# pcb_06.net
KiCad netlist of a schematic drawn in EAGLE
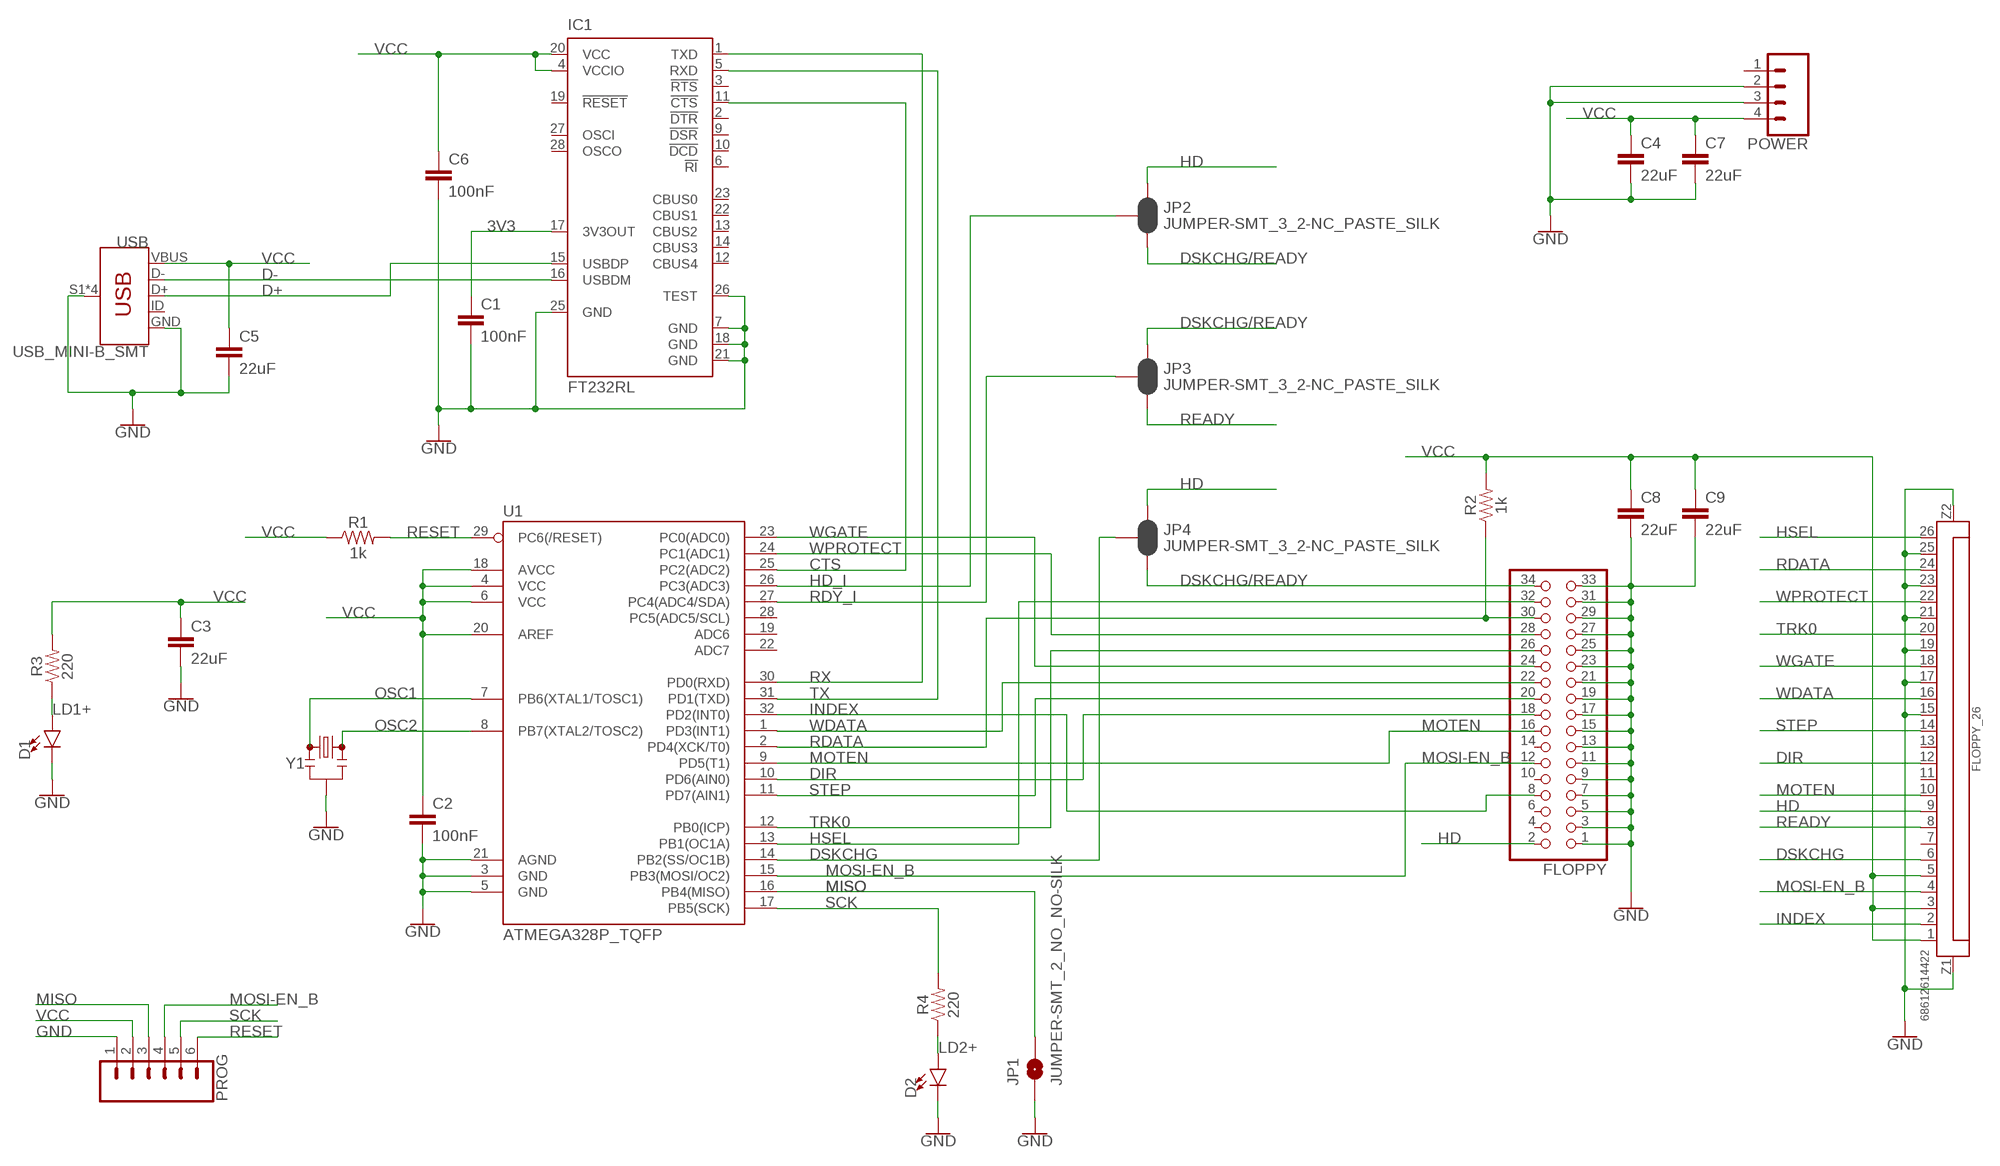
[diagram p0: schematic, sheet 1]

(export (version "E")
  (design (tool "Eeschema 10.0.6"))
  (components
    (comp (ref "C1")
      (value "100nF")
      (footprint "eagle-import:0603")
      (libsource (lib "eagle-import") (part "1.0UF-0603-16V-10%"))
    )
    (comp (ref "C2")
      (value "100nF")
      (footprint "eagle-import:0603")
      (libsource (lib "eagle-import") (part "1.0UF-0603-16V-10%"))
    )
    (comp (ref "C3")
      (value "22uF")
      (footprint "eagle-import:C0805")
      (libsource (lib "eagle-import") (part "C-EUC0805"))
    )
    (comp (ref "C4")
      (value "22uF")
      (footprint "eagle-import:C0805")
      (libsource (lib "eagle-import") (part "C-EUC0805"))
    )
    (comp (ref "C5")
      (value "22uF")
      (footprint "eagle-import:C0805")
      (libsource (lib "eagle-import") (part "C-EUC0805"))
    )
    (comp (ref "C6")
      (value "100nF")
      (footprint "eagle-import:0603")
      (libsource (lib "eagle-import") (part "1.0UF-0603-16V-10%"))
    )
    (comp (ref "C7")
      (value "22uF")
      (footprint "eagle-import:C0805")
      (libsource (lib "eagle-import") (part "C-EUC0805"))
    )
    (comp (ref "C8")
      (value "22uF")
      (footprint "eagle-import:C0805")
      (libsource (lib "eagle-import") (part "C-EUC0805"))
    )
    (comp (ref "C9")
      (value "22uF")
      (footprint "eagle-import:C0805")
      (libsource (lib "eagle-import") (part "C-EUC0805"))
    )
    (comp (ref "D1")
      (value "LED5MM")
      (footprint "eagle-import:LED_5MM")
      (libsource (lib "eagle-import") (part "LED5MM"))
    )
    (comp (ref "D2")
      (value "LED5MM")
      (footprint "eagle-import:LED_5MM")
      (libsource (lib "eagle-import") (part "LED5MM"))
    )
    (comp (ref "FLOPPY")
      (value "PINHD-2X17_2.54-90°")
      (footprint "eagle-import:2X17_90")
      (libsource (lib "eagle-import") (part "PINHD-2X17_2.54-90°"))
    )
    (comp (ref "FLOPPY_26")
      (value "68612614422")
      (footprint "eagle-import:68612614422")
      (libsource (lib "eagle-import") (part "6861XX14422_68612614422"))
    )
    (comp (ref "IC1")
      (value "FT232RL")
      (footprint "eagle-import:SSOP28")
      (libsource (lib "eagle-import") (part "FT232RL"))
    )
    (comp (ref "JP1")
      (value "JUMPER-SMT_2_NO_NO-SILK")
      (footprint "eagle-import:SMT-JUMPER_2_NO_NO-SILK")
      (libsource (lib "eagle-import") (part "JUMPER-SMT_2_NO_NO-SILK"))
    )
    (comp (ref "JP2")
      (value "JUMPER-SMT_3_2-NC_PASTE_SILK")
      (footprint "eagle-import:SMT-JUMPER_3_2-NC_PASTE_SILK")
      (libsource (lib "eagle-import") (part "JUMPER-SMT_3_2-NC_PASTE_SILK"))
    )
    (comp (ref "JP3")
      (value "JUMPER-SMT_3_2-NC_PASTE_SILK")
      (footprint "eagle-import:SMT-JUMPER_3_2-NC_PASTE_SILK")
      (libsource (lib "eagle-import") (part "JUMPER-SMT_3_2-NC_PASTE_SILK"))
    )
    (comp (ref "JP4")
      (value "JUMPER-SMT_3_2-NC_PASTE_SILK")
      (footprint "eagle-import:SMT-JUMPER_3_2-NC_PASTE_SILK")
      (libsource (lib "eagle-import") (part "JUMPER-SMT_3_2-NC_PASTE_SILK"))
    )
    (comp (ref "POWER")
      (value "CONN_04")
      (footprint "eagle-import:1X04")
      (libsource (lib "eagle-import") (part "CONN_04"))
    )
    (comp (ref "PROG")
      (value "CONN_06SILK_FEMALE_PTH")
      (footprint "eagle-import:1X06")
      (libsource (lib "eagle-import") (part "CONN_06SILK_FEMALE_PTH"))
    )
    (comp (ref "R1")
      (value "1k")
      (footprint "eagle-import:0603")
      (libsource (lib "eagle-import") (part "10KOHM-0603-1/10W-1%"))
    )
    (comp (ref "R2")
      (value "1k")
      (footprint "eagle-import:0603")
      (libsource (lib "eagle-import") (part "10KOHM-0603-1/10W-1%"))
    )
    (comp (ref "R3")
      (value "220")
      (footprint "eagle-import:0603")
      (libsource (lib "eagle-import") (part "10KOHM-0603-1/10W-1%"))
    )
    (comp (ref "R4")
      (value "220")
      (footprint "eagle-import:0603")
      (libsource (lib "eagle-import") (part "10KOHM-0603-1/10W-1%"))
    )
    (comp (ref "U1")
      (value "ATMEGA328P_TQFP")
      (footprint "eagle-import:TQFP32-08")
      (libsource (lib "eagle-import") (part "ATMEGA328P_TQFP"))
    )
    (comp (ref "USB")
      (value "USB_MINI-B_SMT")
      (footprint "eagle-import:USB-MINIB")
      (libsource (lib "eagle-import") (part "USB_MINI-B_SMT"))
    )
    (comp (ref "Y1")
      (value "RESONATORSMD-3.2X1.3")
      (footprint "eagle-import:RESONATOR-SMD-3.2X1.3")
      (libsource (lib "eagle-import") (part "RESONATORSMD-3.2X1.3"))
    )
  )
  (nets
    (net (code "1") (name "/3V3") (class "Default")
      (node (ref "C1") (pin "1") (pinfunction "1_1") (pintype "passive"))
      (node (ref "IC1") (pin "17") (pinfunction "3V3OUT_17") (pintype "output"))
    )
    (net (code "2") (name "/CTS") (class "Default")
      (node (ref "IC1") (pin "11") (pinfunction "~{CTS}_11") (pintype "input"))
      (node (ref "U1") (pin "25") (pinfunction "PC2(ADC2)_25") (pintype "bidirectional"))
    )
    (net (code "3") (name "/D+") (class "Default")
      (node (ref "IC1") (pin "15") (pinfunction "USBDP_15") (pintype "bidirectional"))
      (node (ref "USB") (pin "D+") (pinfunction "D+_D+") (pintype "bidirectional"))
    )
    (net (code "4") (name "/D-") (class "Default")
      (node (ref "IC1") (pin "16") (pinfunction "USBDM_16") (pintype "bidirectional"))
      (node (ref "USB") (pin "D-") (pinfunction "D-_D-") (pintype "bidirectional"))
    )
    (net (code "5") (name "/DIR") (class "Default")
      (node (ref "FLOPPY") (pin "18") (pinfunction "18_18") (pintype "passive"))
      (node (ref "FLOPPY_26") (pin "12") (pinfunction "12_12") (pintype "passive"))
      (node (ref "U1") (pin "10") (pinfunction "PD6(AIN0)_10") (pintype "bidirectional"))
    )
    (net (code "6") (name "/DSKCHG") (class "Default")
      (node (ref "FLOPPY_26") (pin "6") (pinfunction "6_6") (pintype "passive"))
      (node (ref "JP4") (pin "2") (pinfunction "2_2") (pintype "passive"))
      (node (ref "U1") (pin "14") (pinfunction "PB2(SS/OC1B)_14") (pintype "bidirectional"))
    )
    (net (code "7") (name "/DSKCHG{slash}READY") (class "Default")
      (node (ref "FLOPPY") (pin "34") (pinfunction "34_34") (pintype "passive"))
      (node (ref "JP2") (pin "3") (pinfunction "3_3") (pintype "passive"))
      (node (ref "JP3") (pin "1") (pinfunction "1_1") (pintype "passive"))
      (node (ref "JP4") (pin "3") (pinfunction "3_3") (pintype "passive"))
    )
    (net (code "8") (name "/HD") (class "Default")
      (node (ref "FLOPPY") (pin "2") (pinfunction "2_2") (pintype "passive"))
      (node (ref "FLOPPY_26") (pin "9") (pinfunction "9_9") (pintype "passive"))
      (node (ref "JP2") (pin "1") (pinfunction "1_1") (pintype "passive"))
      (node (ref "JP4") (pin "1") (pinfunction "1_1") (pintype "passive"))
    )
    (net (code "9") (name "/HD_I") (class "Default")
      (node (ref "JP2") (pin "2") (pinfunction "2_2") (pintype "passive"))
      (node (ref "U1") (pin "26") (pinfunction "PC3(ADC3)_26") (pintype "bidirectional"))
    )
    (net (code "10") (name "/HSEL") (class "Default")
      (node (ref "FLOPPY") (pin "32") (pinfunction "32_32") (pintype "passive"))
      (node (ref "FLOPPY_26") (pin "26") (pinfunction "26_26") (pintype "passive"))
      (node (ref "U1") (pin "13") (pinfunction "PB1(OC1A)_13") (pintype "bidirectional"))
    )
    (net (code "11") (name "/INDEX") (class "Default")
      (node (ref "FLOPPY") (pin "8") (pinfunction "8_8") (pintype "passive"))
      (node (ref "FLOPPY_26") (pin "2") (pinfunction "2_2") (pintype "passive"))
      (node (ref "U1") (pin "32") (pinfunction "PD2(INT0)_32") (pintype "bidirectional"))
    )
    (net (code "12") (name "/LD1+") (class "Default")
      (node (ref "D1") (pin "A") (pinfunction "A_A") (pintype "passive"))
      (node (ref "R3") (pin "1") (pinfunction "1_1") (pintype "passive"))
    )
    (net (code "13") (name "/LD2+") (class "Default")
      (node (ref "D2") (pin "A") (pinfunction "A_A") (pintype "passive"))
      (node (ref "R4") (pin "1") (pinfunction "1_1") (pintype "passive"))
    )
    (net (code "14") (name "/MISO") (class "Default")
      (node (ref "JP1") (pin "2") (pinfunction "2_2") (pintype "passive"))
      (node (ref "PROG") (pin "3") (pinfunction "3_3") (pintype "passive"))
      (node (ref "U1") (pin "16") (pinfunction "PB4(MISO)_16") (pintype "bidirectional"))
    )
    (net (code "15") (name "/MOSI-EN_B") (class "Default")
      (node (ref "FLOPPY") (pin "12") (pinfunction "12_12") (pintype "passive"))
      (node (ref "FLOPPY_26") (pin "4") (pinfunction "4_4") (pintype "passive"))
      (node (ref "PROG") (pin "4") (pinfunction "4_4") (pintype "passive"))
      (node (ref "U1") (pin "15") (pinfunction "PB3(MOSI/OC2)_15") (pintype "bidirectional"))
    )
    (net (code "16") (name "/MOTEN") (class "Default")
      (node (ref "FLOPPY") (pin "16") (pinfunction "16_16") (pintype "passive"))
      (node (ref "FLOPPY_26") (pin "10") (pinfunction "10_10") (pintype "passive"))
      (node (ref "U1") (pin "9") (pinfunction "PD5(T1)_9") (pintype "bidirectional"))
    )
    (net (code "17") (name "/OSC1") (class "Default")
      (node (ref "U1") (pin "7") (pinfunction "PB6(XTAL1/TOSC1)_7") (pintype "bidirectional"))
      (node (ref "Y1") (pin "1") (pinfunction "1_1") (pintype "passive"))
    )
    (net (code "18") (name "/OSC2") (class "Default")
      (node (ref "U1") (pin "8") (pinfunction "PB7(XTAL2/TOSC2)_8") (pintype "bidirectional"))
      (node (ref "Y1") (pin "3") (pinfunction "3_3") (pintype "passive"))
    )
    (net (code "19") (name "/RDATA") (class "Default")
      (node (ref "FLOPPY") (pin "30") (pinfunction "30_30") (pintype "passive"))
      (node (ref "FLOPPY_26") (pin "24") (pinfunction "24_24") (pintype "passive"))
      (node (ref "R2") (pin "1") (pinfunction "1_1") (pintype "passive"))
      (node (ref "U1") (pin "2") (pinfunction "PD4(XCK/T0)_2") (pintype "bidirectional"))
    )
    (net (code "20") (name "/RDY_I") (class "Default")
      (node (ref "JP3") (pin "2") (pinfunction "2_2") (pintype "passive"))
      (node (ref "U1") (pin "27") (pinfunction "PC4(ADC4/SDA)_27") (pintype "bidirectional"))
    )
    (net (code "21") (name "/READY") (class "Default")
      (node (ref "FLOPPY_26") (pin "8") (pinfunction "8_8") (pintype "passive"))
      (node (ref "JP3") (pin "3") (pinfunction "3_3") (pintype "passive"))
    )
    (net (code "22") (name "/RESET") (class "Default")
      (node (ref "PROG") (pin "6") (pinfunction "6_6") (pintype "passive"))
      (node (ref "R1") (pin "2") (pinfunction "2_2") (pintype "passive"))
      (node (ref "U1") (pin "29") (pinfunction "PC6(/RESET)_29") (pintype "bidirectional"))
    )
    (net (code "23") (name "/RX") (class "Default")
      (node (ref "IC1") (pin "1") (pinfunction "TXD_1") (pintype "output"))
      (node (ref "U1") (pin "30") (pinfunction "PD0(RXD)_30") (pintype "bidirectional"))
    )
    (net (code "24") (name "/SCK") (class "Default")
      (node (ref "PROG") (pin "5") (pinfunction "5_5") (pintype "passive"))
      (node (ref "R4") (pin "2") (pinfunction "2_2") (pintype "passive"))
      (node (ref "U1") (pin "17") (pinfunction "PB5(SCK)_17") (pintype "bidirectional"))
    )
    (net (code "25") (name "/STEP") (class "Default")
      (node (ref "FLOPPY") (pin "20") (pinfunction "20_20") (pintype "passive"))
      (node (ref "FLOPPY_26") (pin "14") (pinfunction "14_14") (pintype "passive"))
      (node (ref "U1") (pin "11") (pinfunction "PD7(AIN1)_11") (pintype "bidirectional"))
    )
    (net (code "26") (name "/TRK0") (class "Default")
      (node (ref "FLOPPY") (pin "26") (pinfunction "26_26") (pintype "passive"))
      (node (ref "FLOPPY_26") (pin "20") (pinfunction "20_20") (pintype "passive"))
      (node (ref "U1") (pin "12") (pinfunction "PB0(ICP)_12") (pintype "bidirectional"))
    )
    (net (code "27") (name "/TX") (class "Default")
      (node (ref "IC1") (pin "5") (pinfunction "RXD_5") (pintype "input"))
      (node (ref "U1") (pin "31") (pinfunction "PD1(TXD)_31") (pintype "bidirectional"))
    )
    (net (code "28") (name "/VCC") (class "Default")
      (node (ref "C2") (pin "1") (pinfunction "1_1") (pintype "passive"))
      (node (ref "C3") (pin "1") (pinfunction "1_1") (pintype "passive"))
      (node (ref "C4") (pin "1") (pinfunction "1_1") (pintype "passive"))
      (node (ref "C5") (pin "1") (pinfunction "1_1") (pintype "passive"))
      (node (ref "C6") (pin "1") (pinfunction "1_1") (pintype "passive"))
      (node (ref "C7") (pin "1") (pinfunction "1_1") (pintype "passive"))
      (node (ref "C8") (pin "1") (pinfunction "1_1") (pintype "passive"))
      (node (ref "C9") (pin "1") (pinfunction "1_1") (pintype "passive"))
      (node (ref "FLOPPY_26") (pin "1") (pinfunction "1_1") (pintype "passive"))
      (node (ref "FLOPPY_26") (pin "3") (pinfunction "3_3") (pintype "passive"))
      (node (ref "FLOPPY_26") (pin "5") (pinfunction "5_5") (pintype "passive"))
      (node (ref "IC1") (pin "20") (pinfunction "VCC_20") (pintype "power_in"))
      (node (ref "IC1") (pin "4") (pinfunction "VCCIO_4") (pintype "power_in"))
      (node (ref "POWER") (pin "4") (pinfunction "4_4") (pintype "passive"))
      (node (ref "PROG") (pin "2") (pinfunction "2_2") (pintype "passive"))
      (node (ref "R1") (pin "1") (pinfunction "1_1") (pintype "passive"))
      (node (ref "R2") (pin "2") (pinfunction "2_2") (pintype "passive"))
      (node (ref "R3") (pin "2") (pinfunction "2_2") (pintype "passive"))
      (node (ref "U1") (pin "18") (pinfunction "AVCC_18") (pintype "bidirectional"))
      (node (ref "U1") (pin "20") (pinfunction "AREF_20") (pintype "bidirectional"))
      (node (ref "U1") (pin "4") (pinfunction "VCC_4") (pintype "bidirectional"))
      (node (ref "U1") (pin "6") (pinfunction "VCC_6") (pintype "bidirectional"))
      (node (ref "USB") (pin "VBUS") (pinfunction "VBUS_VBUS") (pintype "power_in"))
    )
    (net (code "29") (name "/WDATA") (class "Default")
      (node (ref "FLOPPY") (pin "22") (pinfunction "22_22") (pintype "passive"))
      (node (ref "FLOPPY_26") (pin "16") (pinfunction "16_16") (pintype "passive"))
      (node (ref "U1") (pin "1") (pinfunction "PD3(INT1)_1") (pintype "bidirectional"))
    )
    (net (code "30") (name "/WGATE") (class "Default")
      (node (ref "FLOPPY") (pin "24") (pinfunction "24_24") (pintype "passive"))
      (node (ref "FLOPPY_26") (pin "18") (pinfunction "18_18") (pintype "passive"))
      (node (ref "U1") (pin "23") (pinfunction "PC0(ADC0)_23") (pintype "bidirectional"))
    )
    (net (code "31") (name "/WPROTECT") (class "Default")
      (node (ref "FLOPPY") (pin "28") (pinfunction "28_28") (pintype "passive"))
      (node (ref "FLOPPY_26") (pin "22") (pinfunction "22_22") (pintype "passive"))
      (node (ref "U1") (pin "24") (pinfunction "PC1(ADC1)_24") (pintype "bidirectional"))
    )
    (net (code "32") (name "GND") (class "Default")
      (node (ref "C1") (pin "2") (pinfunction "2_2") (pintype "passive"))
      (node (ref "C2") (pin "2") (pinfunction "2_2") (pintype "passive"))
      (node (ref "C3") (pin "2") (pinfunction "2_2") (pintype "passive"))
      (node (ref "C4") (pin "2") (pinfunction "2_2") (pintype "passive"))
      (node (ref "C5") (pin "2") (pinfunction "2_2") (pintype "passive"))
      (node (ref "C6") (pin "2") (pinfunction "2_2") (pintype "passive"))
      (node (ref "C7") (pin "2") (pinfunction "2_2") (pintype "passive"))
      (node (ref "C8") (pin "2") (pinfunction "2_2") (pintype "passive"))
      (node (ref "C9") (pin "2") (pinfunction "2_2") (pintype "passive"))
      (node (ref "D1") (pin "K") (pinfunction "C_K") (pintype "passive"))
      (node (ref "D2") (pin "K") (pinfunction "C_K") (pintype "passive"))
      (node (ref "FLOPPY") (pin "1") (pinfunction "1_1") (pintype "passive"))
      (node (ref "FLOPPY") (pin "11") (pinfunction "11_11") (pintype "passive"))
      (node (ref "FLOPPY") (pin "13") (pinfunction "13_13") (pintype "passive"))
      (node (ref "FLOPPY") (pin "15") (pinfunction "15_15") (pintype "passive"))
      (node (ref "FLOPPY") (pin "17") (pinfunction "17_17") (pintype "passive"))
      (node (ref "FLOPPY") (pin "19") (pinfunction "19_19") (pintype "passive"))
      (node (ref "FLOPPY") (pin "21") (pinfunction "21_21") (pintype "passive"))
      (node (ref "FLOPPY") (pin "23") (pinfunction "23_23") (pintype "passive"))
      (node (ref "FLOPPY") (pin "25") (pinfunction "25_25") (pintype "passive"))
      (node (ref "FLOPPY") (pin "27") (pinfunction "27_27") (pintype "passive"))
      (node (ref "FLOPPY") (pin "29") (pinfunction "29_29") (pintype "passive"))
      (node (ref "FLOPPY") (pin "3") (pinfunction "3_3") (pintype "passive"))
      (node (ref "FLOPPY") (pin "31") (pinfunction "31_31") (pintype "passive"))
      (node (ref "FLOPPY") (pin "33") (pinfunction "33_33") (pintype "passive"))
      (node (ref "FLOPPY") (pin "5") (pinfunction "5_5") (pintype "passive"))
      (node (ref "FLOPPY") (pin "7") (pinfunction "7_7") (pintype "passive"))
      (node (ref "FLOPPY") (pin "9") (pinfunction "9_9") (pintype "passive"))
      (node (ref "FLOPPY_26") (pin "15") (pinfunction "15_15") (pintype "passive"))
      (node (ref "FLOPPY_26") (pin "17") (pinfunction "17_17") (pintype "passive"))
      (node (ref "FLOPPY_26") (pin "19") (pinfunction "19_19") (pintype "passive"))
      (node (ref "FLOPPY_26") (pin "21") (pinfunction "21_21") (pintype "passive"))
      (node (ref "FLOPPY_26") (pin "23") (pinfunction "23_23") (pintype "passive"))
      (node (ref "FLOPPY_26") (pin "25") (pinfunction "25_25") (pintype "passive"))
      (node (ref "FLOPPY_26") (pin "Z1") (pinfunction "Z1_Z1") (pintype "passive"))
      (node (ref "FLOPPY_26") (pin "Z2") (pinfunction "Z2_Z2") (pintype "passive"))
      (node (ref "IC1") (pin "18") (pinfunction "GND_18") (pintype "power_in"))
      (node (ref "IC1") (pin "21") (pinfunction "GND_21") (pintype "power_in"))
      (node (ref "IC1") (pin "25") (pinfunction "GND_25") (pintype "power_in"))
      (node (ref "IC1") (pin "26") (pinfunction "TEST_26") (pintype "input"))
      (node (ref "IC1") (pin "7") (pinfunction "GND_7") (pintype "power_in"))
      (node (ref "JP1") (pin "1") (pinfunction "1_1") (pintype "passive"))
      (node (ref "POWER") (pin "2") (pinfunction "2_2") (pintype "passive"))
      (node (ref "POWER") (pin "3") (pinfunction "3_3") (pintype "passive"))
      (node (ref "PROG") (pin "1") (pinfunction "1_1") (pintype "passive"))
      (node (ref "U1") (pin "21") (pinfunction "AGND_21") (pintype "bidirectional"))
      (node (ref "U1") (pin "3") (pinfunction "GND_3") (pintype "bidirectional"))
      (node (ref "U1") (pin "5") (pinfunction "GND_5") (pintype "bidirectional"))
      (node (ref "USB") (pin "GND") (pinfunction "GND_GND") (pintype "power_in"))
      (node (ref "USB") (pin "S1") (pinfunction "SHIELD_S1") (pintype "bidirectional"))
      (node (ref "USB") (pin "S2") (pinfunction "SHIELD_S2") (pintype "bidirectional"))
      (node (ref "USB") (pin "S3") (pinfunction "SHIELD_S3") (pintype "bidirectional"))
      (node (ref "USB") (pin "S4") (pinfunction "SHIELD_S4") (pintype "bidirectional"))
      (node (ref "Y1") (pin "2") (pinfunction "2_2") (pintype "passive"))
    )
    (net (code "33") (name "unconnected-(FLOPPY-Pad4)") (class "Default")
      (node (ref "FLOPPY") (pin "4") (pinfunction "4_4") (pintype "passive"))
    )
    (net (code "34") (name "unconnected-(FLOPPY-Pad6)") (class "Default")
      (node (ref "FLOPPY") (pin "6") (pinfunction "6_6") (pintype "passive"))
    )
    (net (code "35") (name "unconnected-(FLOPPY-Pad10)") (class "Default")
      (node (ref "FLOPPY") (pin "10") (pinfunction "10_10") (pintype "passive"))
    )
    (net (code "36") (name "unconnected-(FLOPPY-Pad14)") (class "Default")
      (node (ref "FLOPPY") (pin "14") (pinfunction "14_14") (pintype "passive"))
    )
    (net (code "37") (name "unconnected-(FLOPPY_26-Pad7)") (class "Default")
      (node (ref "FLOPPY_26") (pin "7") (pinfunction "7_7") (pintype "passive"))
    )
    (net (code "38") (name "unconnected-(FLOPPY_26-Pad11)") (class "Default")
      (node (ref "FLOPPY_26") (pin "11") (pinfunction "11_11") (pintype "passive"))
    )
    (net (code "39") (name "unconnected-(FLOPPY_26-Pad13)") (class "Default")
      (node (ref "FLOPPY_26") (pin "13") (pinfunction "13_13") (pintype "passive"))
    )
    (net (code "40") (name "unconnected-(IC1-CBUS0-Pad23)") (class "Default")
      (node (ref "IC1") (pin "23") (pinfunction "CBUS0_23") (pintype "bidirectional"))
    )
    (net (code "41") (name "unconnected-(IC1-CBUS1-Pad22)") (class "Default")
      (node (ref "IC1") (pin "22") (pinfunction "CBUS1_22") (pintype "bidirectional"))
    )
    (net (code "42") (name "unconnected-(IC1-CBUS2-Pad13)") (class "Default")
      (node (ref "IC1") (pin "13") (pinfunction "CBUS2_13") (pintype "bidirectional"))
    )
    (net (code "43") (name "unconnected-(IC1-CBUS3-Pad14)") (class "Default")
      (node (ref "IC1") (pin "14") (pinfunction "CBUS3_14") (pintype "bidirectional"))
    )
    (net (code "44") (name "unconnected-(IC1-CBUS4-Pad12)") (class "Default")
      (node (ref "IC1") (pin "12") (pinfunction "CBUS4_12") (pintype "bidirectional"))
    )
    (net (code "45") (name "unconnected-(IC1-OSCI-Pad27)") (class "Default")
      (node (ref "IC1") (pin "27") (pinfunction "OSCI_27") (pintype "input"))
    )
    (net (code "46") (name "unconnected-(IC1-OSCO-Pad28)") (class "Default")
      (node (ref "IC1") (pin "28") (pinfunction "OSCO_28") (pintype "output"))
    )
    (net (code "47") (name "unconnected-(IC1-~{DCD}-Pad10)") (class "Default")
      (node (ref "IC1") (pin "10") (pinfunction "~{DCD}_10") (pintype "input"))
    )
    (net (code "48") (name "unconnected-(IC1-~{DSR}-Pad9)") (class "Default")
      (node (ref "IC1") (pin "9") (pinfunction "~{DSR}_9") (pintype "input"))
    )
    (net (code "49") (name "unconnected-(IC1-~{DTR}-Pad2)") (class "Default")
      (node (ref "IC1") (pin "2") (pinfunction "~{DTR}_2") (pintype "output"))
    )
    (net (code "50") (name "unconnected-(IC1-~{RESET}-Pad19)") (class "Default")
      (node (ref "IC1") (pin "19") (pinfunction "~{RESET}_19") (pintype "input"))
    )
    (net (code "51") (name "unconnected-(IC1-~{RI}-Pad6)") (class "Default")
      (node (ref "IC1") (pin "6") (pinfunction "~{RI}_6") (pintype "input"))
    )
    (net (code "52") (name "unconnected-(IC1-~{RTS}-Pad3)") (class "Default")
      (node (ref "IC1") (pin "3") (pinfunction "~{RTS}_3") (pintype "output"))
    )
    (net (code "53") (name "unconnected-(POWER-Pad1)") (class "Default")
      (node (ref "POWER") (pin "1") (pinfunction "1_1") (pintype "passive"))
    )
    (net (code "54") (name "unconnected-(U1-ADC6-Pad19)") (class "Default")
      (node (ref "U1") (pin "19") (pinfunction "ADC6_19") (pintype "bidirectional"))
    )
    (net (code "55") (name "unconnected-(U1-ADC7-Pad22)") (class "Default")
      (node (ref "U1") (pin "22") (pinfunction "ADC7_22") (pintype "bidirectional"))
    )
    (net (code "56") (name "unconnected-(U1-PC5(ADC5{slash}SCL)-Pad28)") (class "Default")
      (node (ref "U1") (pin "28") (pinfunction "PC5(ADC5/SCL)_28") (pintype "bidirectional"))
    )
    (net (code "57") (name "unconnected-(USB-PadID)") (class "Default")
      (node (ref "USB") (pin "ID") (pinfunction "ID_ID") (pintype "bidirectional"))
    )
  )
)
